# rc-light-controller-tlc5940-lpc812.net
KiCad netlist of a schematic drawn in EAGLE
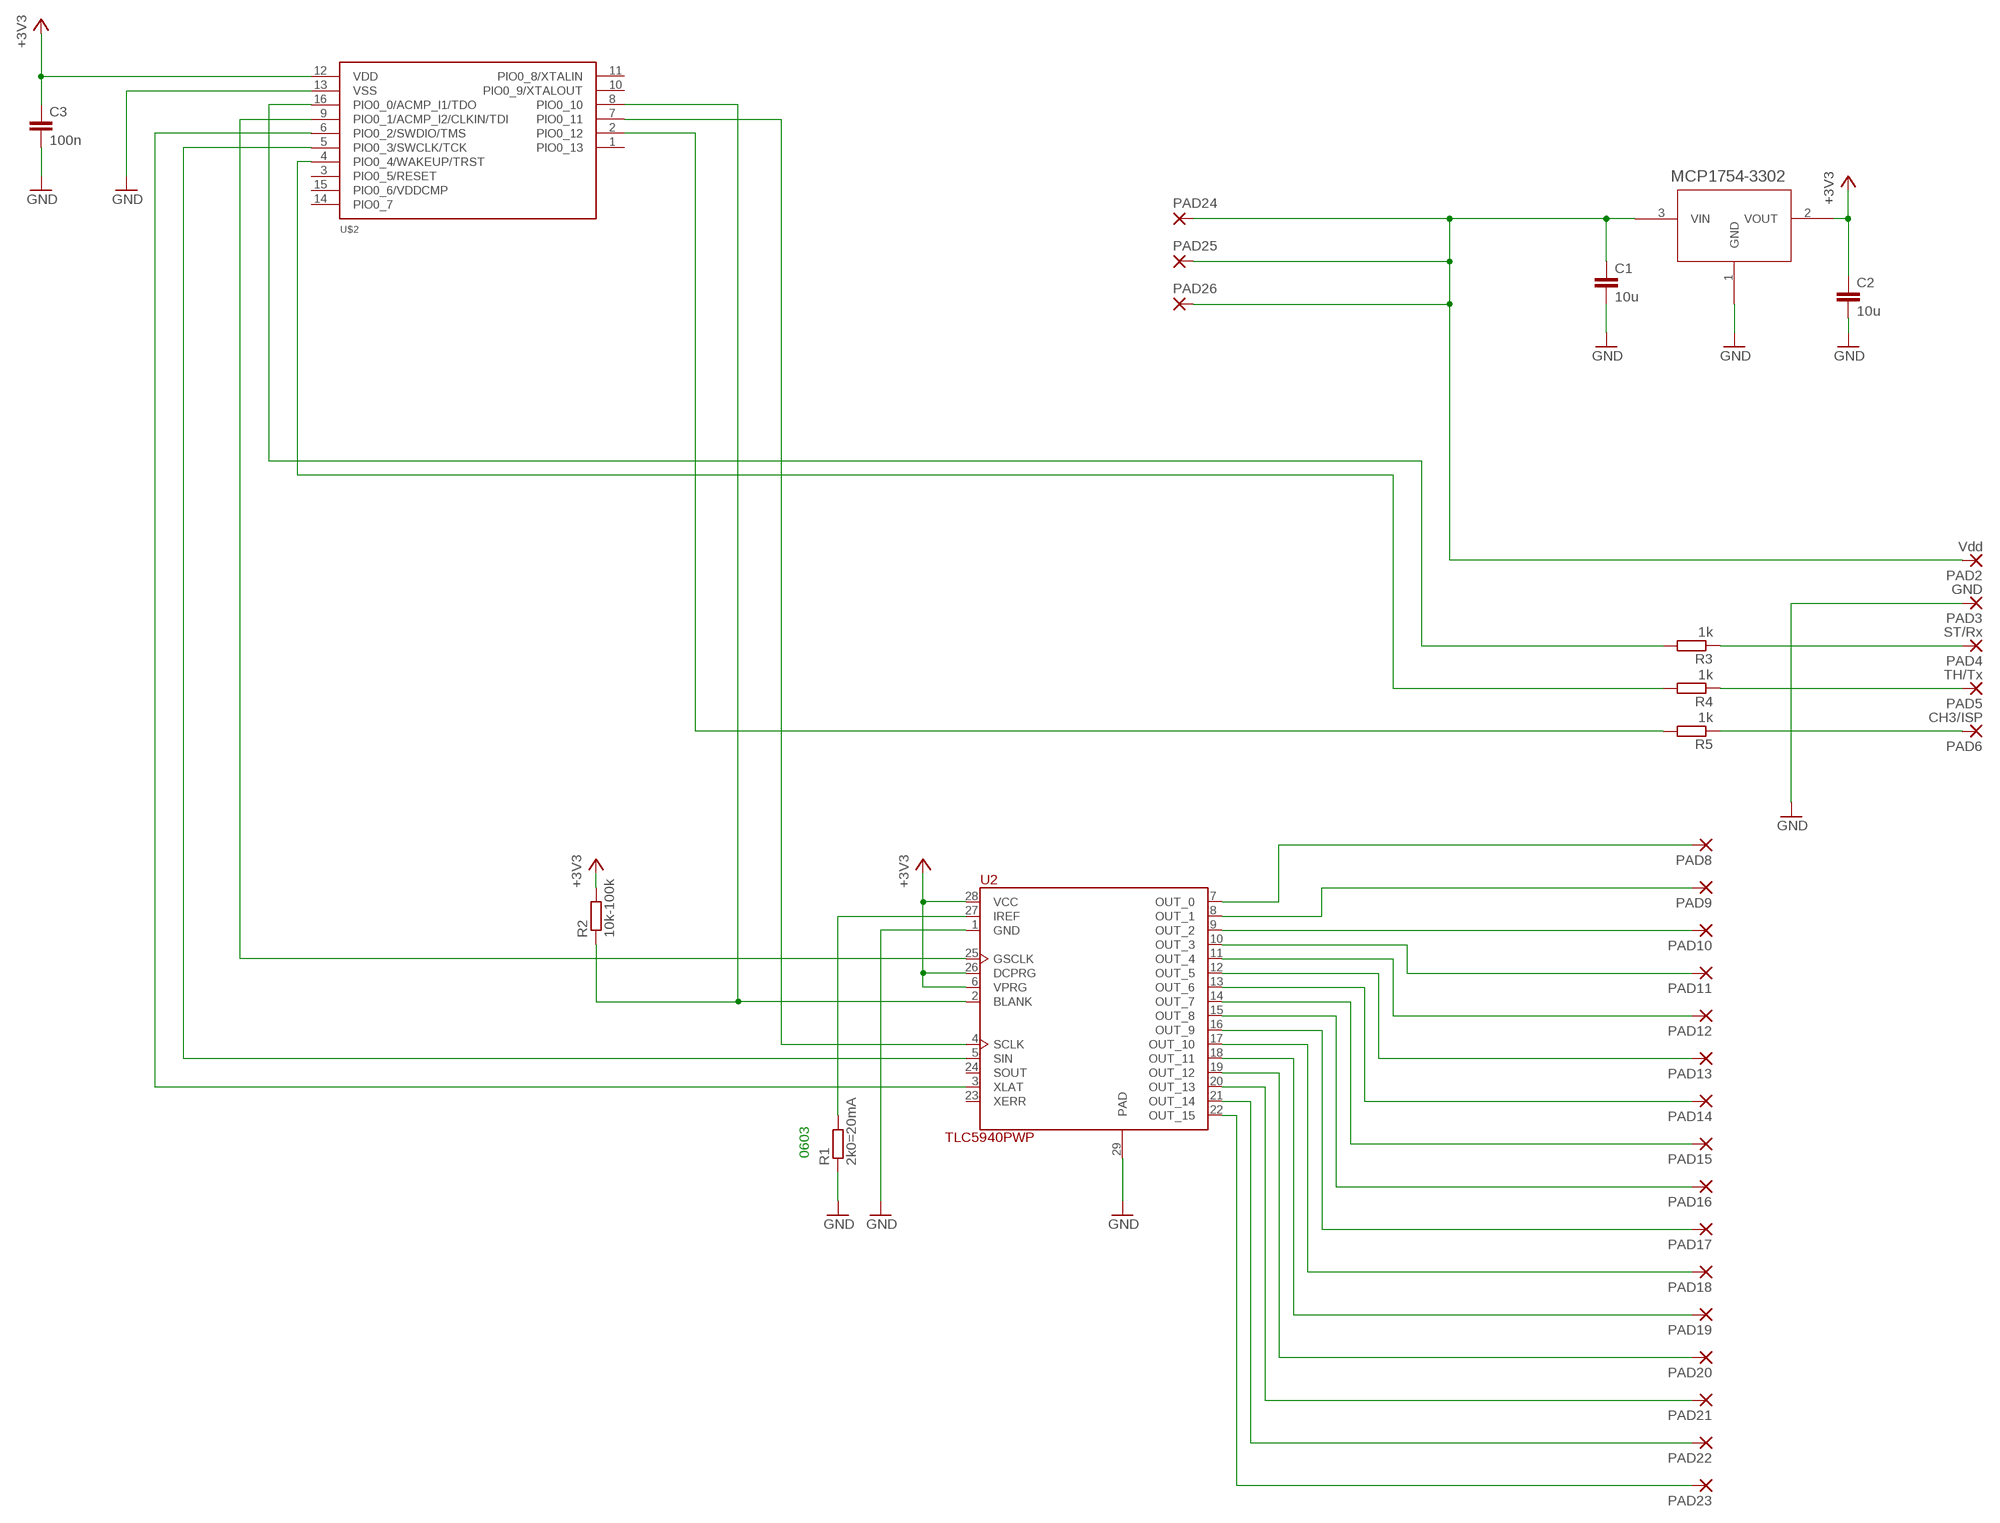
[diagram p0: schematic, sheet 1]

(export (version "E")
  (design (tool "Eeschema 10.0.6"))
  (components
    (comp (ref "C1")
      (value "10u")
      (footprint "eagle-import:C0805")
      (libsource (lib "eagle-import") (part "C-EUC0805"))
    )
    (comp (ref "C2")
      (value "10u")
      (footprint "eagle-import:C0805")
      (libsource (lib "eagle-import") (part "C-EUC0805"))
    )
    (comp (ref "C3")
      (value "100n")
      (footprint "eagle-import:C0805")
      (libsource (lib "eagle-import") (part "C-EUC0805"))
    )
    (comp (ref "PAD2")
      (value "Vdd")
      (footprint "eagle-import:SMD80X120")
      (libsource (lib "eagle-import") (part "SDM80X120"))
    )
    (comp (ref "PAD3")
      (value "GND")
      (footprint "eagle-import:SMD80X120")
      (libsource (lib "eagle-import") (part "SDM80X120"))
    )
    (comp (ref "PAD4")
      (value "ST/Rx")
      (footprint "eagle-import:SMD80X120")
      (libsource (lib "eagle-import") (part "SDM80X120"))
    )
    (comp (ref "PAD5")
      (value "TH/Tx")
      (footprint "eagle-import:SMD80X120")
      (libsource (lib "eagle-import") (part "SDM80X120"))
    )
    (comp (ref "PAD6")
      (value "CH3/ISP")
      (footprint "eagle-import:SMD80X120")
      (libsource (lib "eagle-import") (part "SDM80X120"))
    )
    (comp (ref "PAD8")
      (value "SMD50X100")
      (footprint "eagle-import:SMD50X100")
      (libsource (lib "eagle-import") (part "SMD50X100"))
    )
    (comp (ref "PAD9")
      (value "SMD50X100")
      (footprint "eagle-import:SMD50X100")
      (libsource (lib "eagle-import") (part "SMD50X100"))
    )
    (comp (ref "PAD10")
      (value "SMD50X100")
      (footprint "eagle-import:SMD50X100")
      (libsource (lib "eagle-import") (part "SMD50X100"))
    )
    (comp (ref "PAD11")
      (value "SMD50X100")
      (footprint "eagle-import:SMD50X100")
      (libsource (lib "eagle-import") (part "SMD50X100"))
    )
    (comp (ref "PAD12")
      (value "SMD50X100")
      (footprint "eagle-import:SMD50X100")
      (libsource (lib "eagle-import") (part "SMD50X100"))
    )
    (comp (ref "PAD13")
      (value "SMD50X100")
      (footprint "eagle-import:SMD50X100")
      (libsource (lib "eagle-import") (part "SMD50X100"))
    )
    (comp (ref "PAD14")
      (value "SMD50X100")
      (footprint "eagle-import:SMD50X100")
      (libsource (lib "eagle-import") (part "SMD50X100"))
    )
    (comp (ref "PAD15")
      (value "SMD50X100")
      (footprint "eagle-import:SMD50X100")
      (libsource (lib "eagle-import") (part "SMD50X100"))
    )
    (comp (ref "PAD16")
      (value "SMD50X100")
      (footprint "eagle-import:SMD50X100")
      (libsource (lib "eagle-import") (part "SMD50X100"))
    )
    (comp (ref "PAD17")
      (value "SMD50X100")
      (footprint "eagle-import:SMD50X100")
      (libsource (lib "eagle-import") (part "SMD50X100"))
    )
    (comp (ref "PAD18")
      (value "SMD50X100")
      (footprint "eagle-import:SMD50X100")
      (libsource (lib "eagle-import") (part "SMD50X100"))
    )
    (comp (ref "PAD19")
      (value "SMD50X100")
      (footprint "eagle-import:SMD50X100")
      (libsource (lib "eagle-import") (part "SMD50X100"))
    )
    (comp (ref "PAD20")
      (value "SMD50X100")
      (footprint "eagle-import:SMD50X100")
      (libsource (lib "eagle-import") (part "SMD50X100"))
    )
    (comp (ref "PAD21")
      (value "SMD50X100")
      (footprint "eagle-import:SMD50X100")
      (libsource (lib "eagle-import") (part "SMD50X100"))
    )
    (comp (ref "PAD22")
      (value "SMD50X100")
      (footprint "eagle-import:SMD50X100")
      (libsource (lib "eagle-import") (part "SMD50X100"))
    )
    (comp (ref "PAD23")
      (value "SMD50X100")
      (footprint "eagle-import:SMD50X100")
      (libsource (lib "eagle-import") (part "SMD50X100"))
    )
    (comp (ref "PAD24")
      (value "SMD50X100")
      (footprint "eagle-import:SMD50X100")
      (libsource (lib "eagle-import") (part "SMD50X100"))
    )
    (comp (ref "PAD25")
      (value "SMD50X100")
      (footprint "eagle-import:SMD50X100")
      (libsource (lib "eagle-import") (part "SMD50X100"))
    )
    (comp (ref "PAD26")
      (value "SMD50X100")
      (footprint "eagle-import:SMD50X100")
      (libsource (lib "eagle-import") (part "SMD50X100"))
    )
    (comp (ref "R1")
      (value "2k0=20mA")
      (footprint "eagle-import:R0805")
      (libsource (lib "eagle-import") (part "R-EU_R0805"))
    )
    (comp (ref "R2")
      (value "10k-100k")
      (footprint "eagle-import:R0805")
      (libsource (lib "eagle-import") (part "R-EU_R0805"))
    )
    (comp (ref "R3")
      (value "1k")
      (footprint "eagle-import:R0805")
      (libsource (lib "eagle-import") (part "R-EU_R0805"))
    )
    (comp (ref "R4")
      (value "1k")
      (footprint "eagle-import:R0805")
      (libsource (lib "eagle-import") (part "R-EU_R0805"))
    )
    (comp (ref "R5")
      (value "1k")
      (footprint "eagle-import:R0805")
      (libsource (lib "eagle-import") (part "R-EU_R0805"))
    )
    (comp (ref "U$1")
      (value "MCP1754X-XXXXX/C")
      (footprint "eagle-import:SOT-23A_MC")
      (libsource (lib "eagle-import") (part "MCP1754X-XXXXX/C"))
    )
    (comp (ref "U$2")
      (value "LPC812")
      (footprint "eagle-import:TSSOP16")
      (libsource (lib "eagle-import") (part "LPC812M101JDH16"))
    )
    (comp (ref "U2")
      (value "TLC5940PWP")
      (footprint "eagle-import:SOP65P640X120-29N")
      (libsource (lib "eagle-import") (part "TLC5940PWP"))
    )
  )
  (nets
    (net (code "1") (name "+3V3") (class "Default")
      (node (ref "C2") (pin "1") (pinfunction "1_1") (pintype "passive"))
      (node (ref "C3") (pin "1") (pinfunction "1_1") (pintype "passive"))
      (node (ref "R2") (pin "2") (pinfunction "2_2") (pintype "passive"))
      (node (ref "U$1") (pin "2") (pinfunction "VOUT_2") (pintype "passive"))
      (node (ref "U$2") (pin "12") (pinfunction "VDD_12") (pintype "bidirectional"))
      (node (ref "U2") (pin "26") (pinfunction "DCPRG_26") (pintype "input"))
      (node (ref "U2") (pin "28") (pinfunction "VCC_28") (pintype "power_in"))
      (node (ref "U2") (pin "6") (pinfunction "VPRG_6") (pintype "input"))
    )
    (net (code "2") (name "GND") (class "Default")
      (node (ref "C1") (pin "2") (pinfunction "2_2") (pintype "passive"))
      (node (ref "C2") (pin "2") (pinfunction "2_2") (pintype "passive"))
      (node (ref "C3") (pin "2") (pinfunction "2_2") (pintype "passive"))
      (node (ref "PAD3") (pin "1") (pinfunction "P_1") (pintype "passive"))
      (node (ref "R1") (pin "1") (pinfunction "1_1") (pintype "passive"))
      (node (ref "U$1") (pin "1") (pinfunction "GND_1") (pintype "passive"))
      (node (ref "U$2") (pin "13") (pinfunction "VSS_13") (pintype "bidirectional"))
      (node (ref "U2") (pin "1") (pinfunction "GND_1") (pintype "power_in"))
      (node (ref "U2") (pin "29") (pinfunction "PAD_29") (pintype "passive"))
    )
    (net (code "3") (name "Net-(PAD2-P)") (class "Default")
      (node (ref "C1") (pin "1") (pinfunction "1_1") (pintype "passive"))
      (node (ref "PAD2") (pin "1") (pinfunction "P_1") (pintype "passive"))
      (node (ref "PAD24") (pin "1") (pinfunction "P_1") (pintype "passive"))
      (node (ref "PAD25") (pin "1") (pinfunction "P_1") (pintype "passive"))
      (node (ref "PAD26") (pin "1") (pinfunction "P_1") (pintype "passive"))
      (node (ref "U$1") (pin "3") (pinfunction "VIN_3") (pintype "passive"))
    )
    (net (code "4") (name "Net-(PAD4-P)") (class "Default")
      (node (ref "PAD4") (pin "1") (pinfunction "P_1") (pintype "passive"))
      (node (ref "R3") (pin "1") (pinfunction "1_1") (pintype "passive"))
    )
    (net (code "5") (name "Net-(PAD5-P)") (class "Default")
      (node (ref "PAD5") (pin "1") (pinfunction "P_1") (pintype "passive"))
      (node (ref "R4") (pin "1") (pinfunction "1_1") (pintype "passive"))
    )
    (net (code "6") (name "Net-(PAD6-P)") (class "Default")
      (node (ref "PAD6") (pin "1") (pinfunction "P_1") (pintype "passive"))
      (node (ref "R5") (pin "1") (pinfunction "1_1") (pintype "passive"))
    )
    (net (code "7") (name "Net-(PAD8-P)") (class "Default")
      (node (ref "PAD8") (pin "1") (pinfunction "P_1") (pintype "passive"))
      (node (ref "U2") (pin "7") (pinfunction "OUT_0_7") (pintype "output"))
    )
    (net (code "8") (name "Net-(PAD9-P)") (class "Default")
      (node (ref "PAD9") (pin "1") (pinfunction "P_1") (pintype "passive"))
      (node (ref "U2") (pin "8") (pinfunction "OUT_1_8") (pintype "output"))
    )
    (net (code "9") (name "Net-(PAD10-P)") (class "Default")
      (node (ref "PAD10") (pin "1") (pinfunction "P_1") (pintype "passive"))
      (node (ref "U2") (pin "9") (pinfunction "OUT_2_9") (pintype "output"))
    )
    (net (code "10") (name "Net-(PAD11-P)") (class "Default")
      (node (ref "PAD11") (pin "1") (pinfunction "P_1") (pintype "passive"))
      (node (ref "U2") (pin "10") (pinfunction "OUT_3_10") (pintype "output"))
    )
    (net (code "11") (name "Net-(PAD12-P)") (class "Default")
      (node (ref "PAD12") (pin "1") (pinfunction "P_1") (pintype "passive"))
      (node (ref "U2") (pin "11") (pinfunction "OUT_4_11") (pintype "output"))
    )
    (net (code "12") (name "Net-(PAD13-P)") (class "Default")
      (node (ref "PAD13") (pin "1") (pinfunction "P_1") (pintype "passive"))
      (node (ref "U2") (pin "12") (pinfunction "OUT_5_12") (pintype "output"))
    )
    (net (code "13") (name "Net-(PAD14-P)") (class "Default")
      (node (ref "PAD14") (pin "1") (pinfunction "P_1") (pintype "passive"))
      (node (ref "U2") (pin "13") (pinfunction "OUT_6_13") (pintype "output"))
    )
    (net (code "14") (name "Net-(PAD15-P)") (class "Default")
      (node (ref "PAD15") (pin "1") (pinfunction "P_1") (pintype "passive"))
      (node (ref "U2") (pin "14") (pinfunction "OUT_7_14") (pintype "output"))
    )
    (net (code "15") (name "Net-(PAD16-P)") (class "Default")
      (node (ref "PAD16") (pin "1") (pinfunction "P_1") (pintype "passive"))
      (node (ref "U2") (pin "15") (pinfunction "OUT_8_15") (pintype "output"))
    )
    (net (code "16") (name "Net-(PAD17-P)") (class "Default")
      (node (ref "PAD17") (pin "1") (pinfunction "P_1") (pintype "passive"))
      (node (ref "U2") (pin "16") (pinfunction "OUT_9_16") (pintype "output"))
    )
    (net (code "17") (name "Net-(PAD18-P)") (class "Default")
      (node (ref "PAD18") (pin "1") (pinfunction "P_1") (pintype "passive"))
      (node (ref "U2") (pin "17") (pinfunction "OUT_10_17") (pintype "output"))
    )
    (net (code "18") (name "Net-(PAD19-P)") (class "Default")
      (node (ref "PAD19") (pin "1") (pinfunction "P_1") (pintype "passive"))
      (node (ref "U2") (pin "18") (pinfunction "OUT_11_18") (pintype "output"))
    )
    (net (code "19") (name "Net-(PAD20-P)") (class "Default")
      (node (ref "PAD20") (pin "1") (pinfunction "P_1") (pintype "passive"))
      (node (ref "U2") (pin "19") (pinfunction "OUT_12_19") (pintype "output"))
    )
    (net (code "20") (name "Net-(PAD21-P)") (class "Default")
      (node (ref "PAD21") (pin "1") (pinfunction "P_1") (pintype "passive"))
      (node (ref "U2") (pin "20") (pinfunction "OUT_13_20") (pintype "output"))
    )
    (net (code "21") (name "Net-(PAD22-P)") (class "Default")
      (node (ref "PAD22") (pin "1") (pinfunction "P_1") (pintype "passive"))
      (node (ref "U2") (pin "21") (pinfunction "OUT_14_21") (pintype "output"))
    )
    (net (code "22") (name "Net-(PAD23-P)") (class "Default")
      (node (ref "PAD23") (pin "1") (pinfunction "P_1") (pintype "passive"))
      (node (ref "U2") (pin "22") (pinfunction "OUT_15_22") (pintype "output"))
    )
    (net (code "23") (name "Net-(U$2-PIO0_0{slash}ACMP_I1{slash}TDO)") (class "Default")
      (node (ref "R3") (pin "2") (pinfunction "2_2") (pintype "passive"))
      (node (ref "U$2") (pin "16") (pinfunction "PIO0_0/ACMP_I1/TDO_16") (pintype "bidirectional"))
    )
    (net (code "24") (name "Net-(U$2-PIO0_1{slash}ACMP_I2{slash}CLKIN{slash}TDI)") (class "Default")
      (node (ref "U$2") (pin "9") (pinfunction "PIO0_1/ACMP_I2/CLKIN/TDI_9") (pintype "bidirectional"))
      (node (ref "U2") (pin "25") (pinfunction "GSCLK_25") (pintype "input"))
    )
    (net (code "25") (name "Net-(U$2-PIO0_2{slash}SWDIO{slash}TMS)") (class "Default")
      (node (ref "U$2") (pin "6") (pinfunction "PIO0_2/SWDIO/TMS_6") (pintype "bidirectional"))
      (node (ref "U2") (pin "3") (pinfunction "XLAT_3") (pintype "input"))
    )
    (net (code "26") (name "Net-(U$2-PIO0_3{slash}SWCLK{slash}TCK)") (class "Default")
      (node (ref "U$2") (pin "5") (pinfunction "PIO0_3/SWCLK/TCK_5") (pintype "bidirectional"))
      (node (ref "U2") (pin "5") (pinfunction "SIN_5") (pintype "input"))
    )
    (net (code "27") (name "Net-(U$2-PIO0_4{slash}WAKEUP{slash}TRST)") (class "Default")
      (node (ref "R4") (pin "2") (pinfunction "2_2") (pintype "passive"))
      (node (ref "U$2") (pin "4") (pinfunction "PIO0_4/WAKEUP/TRST_4") (pintype "bidirectional"))
    )
    (net (code "28") (name "Net-(U$2-PIO0_10)") (class "Default")
      (node (ref "R2") (pin "1") (pinfunction "1_1") (pintype "passive"))
      (node (ref "U$2") (pin "8") (pinfunction "PIO0_10_8") (pintype "bidirectional"))
      (node (ref "U2") (pin "2") (pinfunction "BLANK_2") (pintype "input"))
    )
    (net (code "29") (name "Net-(U$2-PIO0_11)") (class "Default")
      (node (ref "U$2") (pin "7") (pinfunction "PIO0_11_7") (pintype "bidirectional"))
      (node (ref "U2") (pin "4") (pinfunction "SCLK_4") (pintype "input"))
    )
    (net (code "30") (name "Net-(U$2-PIO0_12)") (class "Default")
      (node (ref "R5") (pin "2") (pinfunction "2_2") (pintype "passive"))
      (node (ref "U$2") (pin "2") (pinfunction "PIO0_12_2") (pintype "bidirectional"))
    )
    (net (code "31") (name "Net-(U2-IREF)") (class "Default")
      (node (ref "R1") (pin "2") (pinfunction "2_2") (pintype "passive"))
      (node (ref "U2") (pin "27") (pinfunction "IREF_27") (pintype "power_in"))
    )
    (net (code "32") (name "unconnected-(U$2-PIO0_5{slash}RESET-Pad3)") (class "Default")
      (node (ref "U$2") (pin "3") (pinfunction "PIO0_5/RESET_3") (pintype "bidirectional"))
    )
    (net (code "33") (name "unconnected-(U$2-PIO0_6{slash}VDDCMP-Pad15)") (class "Default")
      (node (ref "U$2") (pin "15") (pinfunction "PIO0_6/VDDCMP_15") (pintype "bidirectional"))
    )
    (net (code "34") (name "unconnected-(U$2-PIO0_7-Pad14)") (class "Default")
      (node (ref "U$2") (pin "14") (pinfunction "PIO0_7_14") (pintype "bidirectional"))
    )
    (net (code "35") (name "unconnected-(U$2-PIO0_8{slash}XTALIN-Pad11)") (class "Default")
      (node (ref "U$2") (pin "11") (pinfunction "PIO0_8/XTALIN_11") (pintype "bidirectional"))
    )
    (net (code "36") (name "unconnected-(U$2-PIO0_9{slash}XTALOUT-Pad10)") (class "Default")
      (node (ref "U$2") (pin "10") (pinfunction "PIO0_9/XTALOUT_10") (pintype "bidirectional"))
    )
    (net (code "37") (name "unconnected-(U$2-PIO0_13-Pad1)") (class "Default")
      (node (ref "U$2") (pin "1") (pinfunction "PIO0_13_1") (pintype "bidirectional"))
    )
    (net (code "38") (name "unconnected-(U2-SOUT-Pad24)") (class "Default")
      (node (ref "U2") (pin "24") (pinfunction "SOUT_24") (pintype "output"))
    )
    (net (code "39") (name "unconnected-(U2-XERR-Pad23)") (class "Default")
      (node (ref "U2") (pin "23") (pinfunction "XERR_23") (pintype "output"))
    )
  )
)
